# FPGA_-_PERIPHERALS.net
KiCad netlist of a schematic drawn in Altium Designer
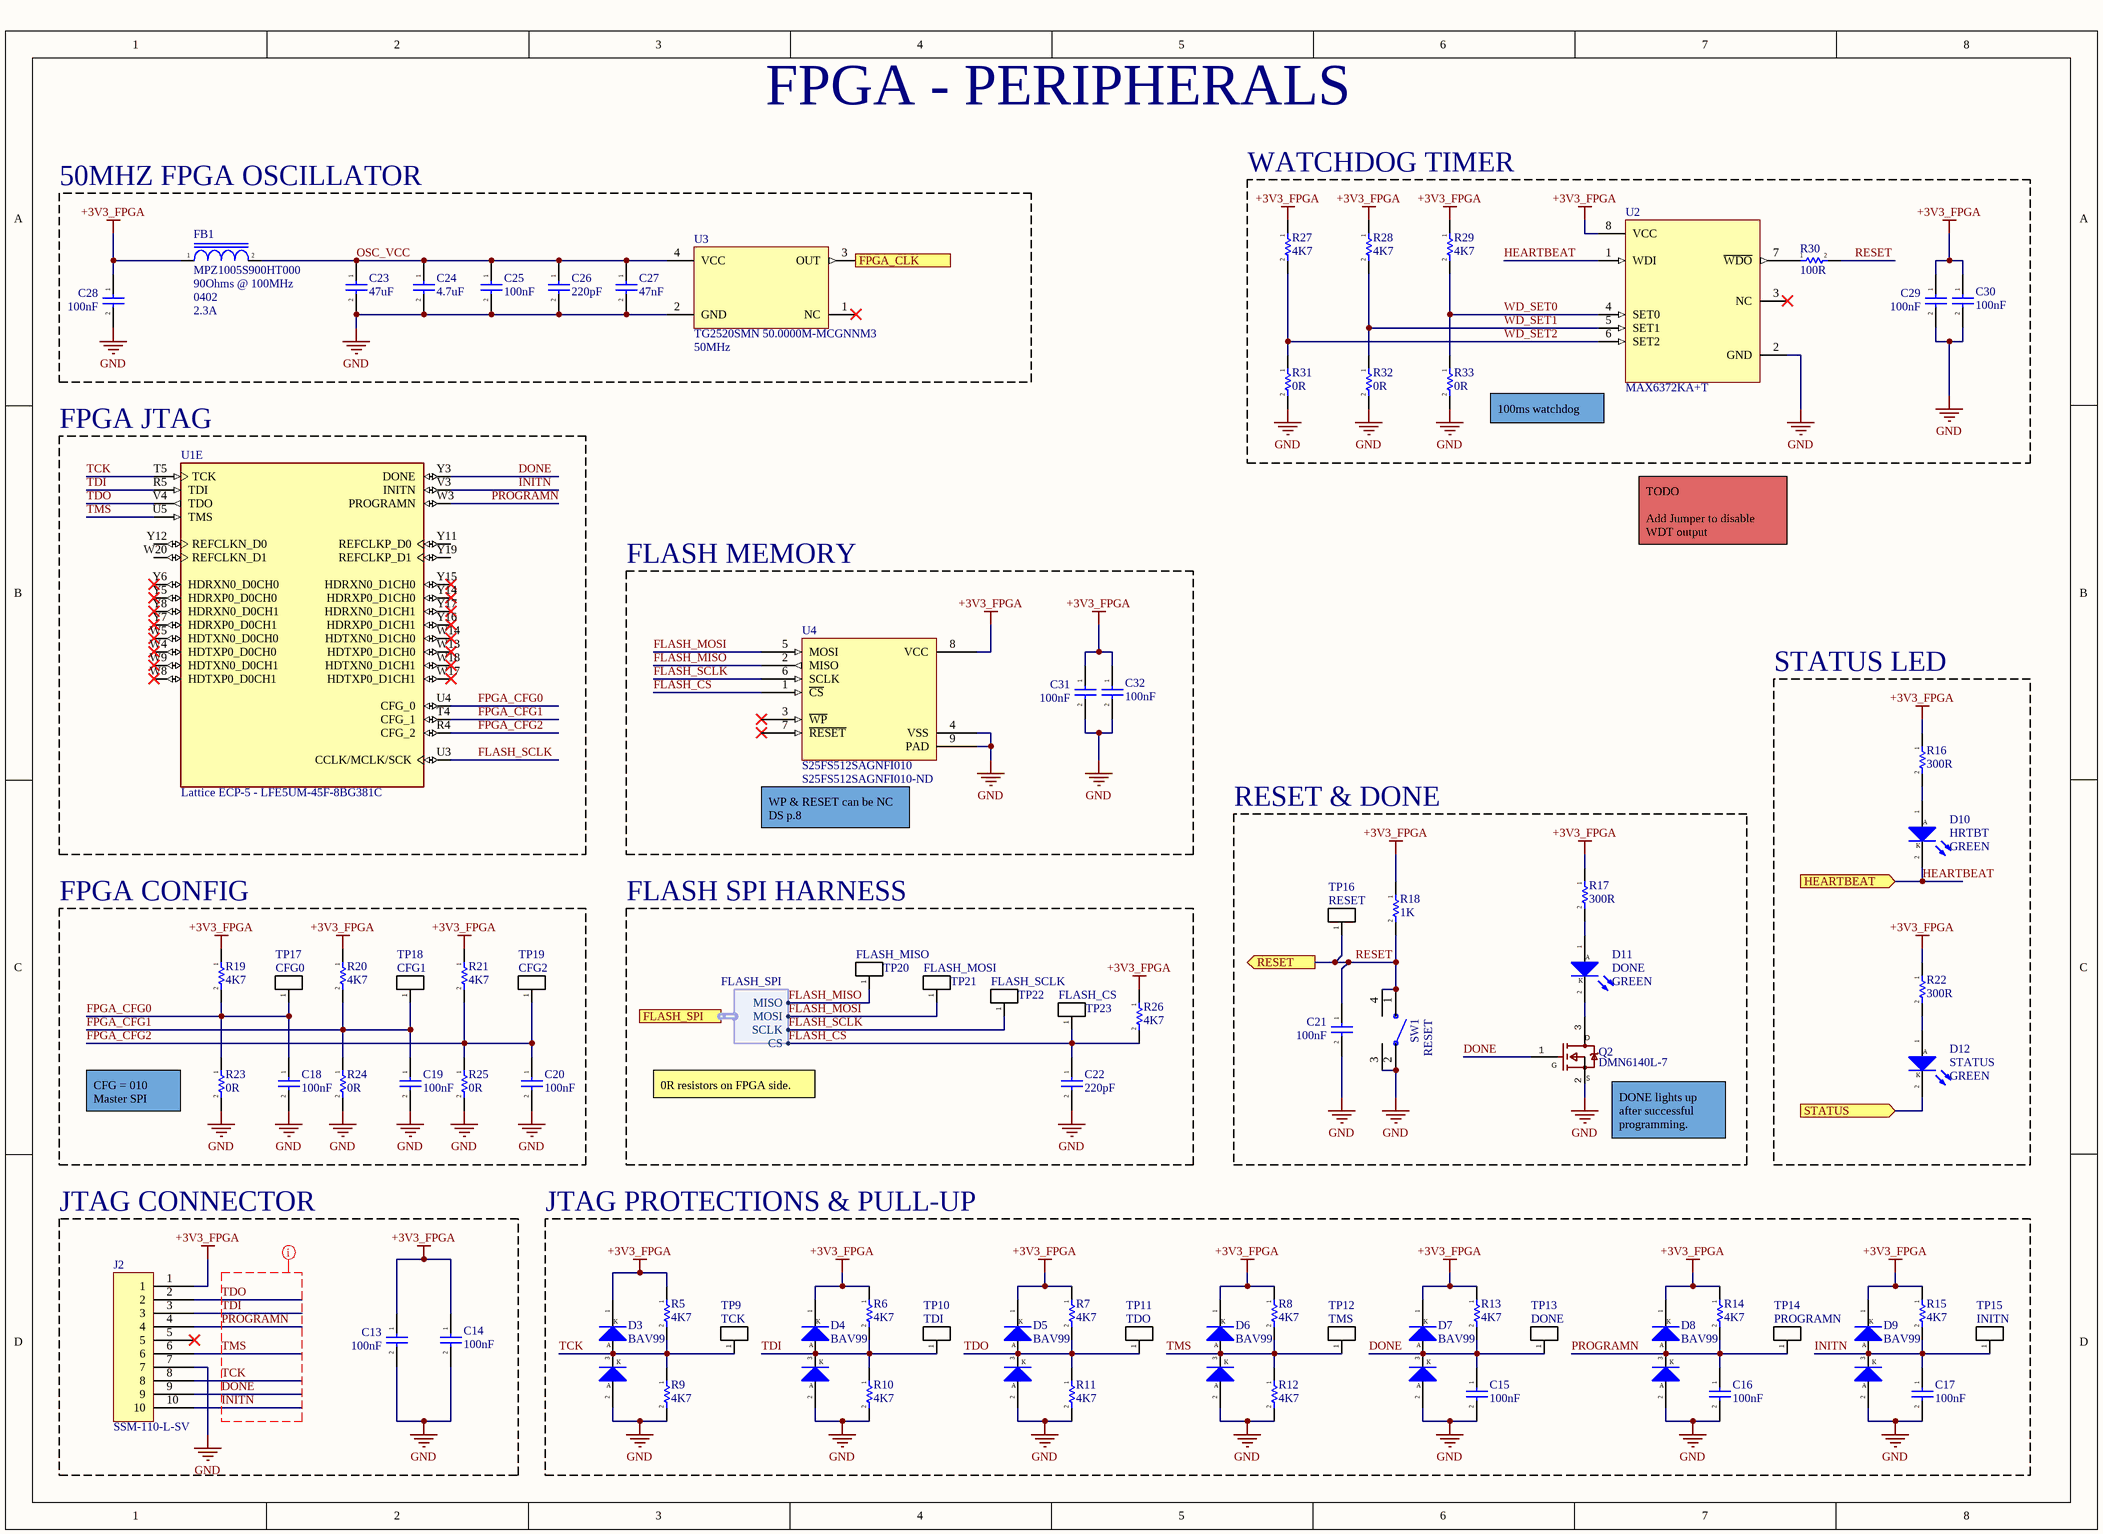
[diagram p0: FPGA - PERIPHERALS.SchDoc]

(export (version "E")
  (design (tool "Eeschema 10.0.6"))
  (components
    (comp (ref "C13")
      (value "100nF")
      (footprint "CAP_0402")
      (description "Generic SMT Ceramic Capacitor")
      (libsource (lib "Symbols") (part "CAP_CER"))
    )
    (comp (ref "C14")
      (value "100nF")
      (footprint "CAP_0402")
      (description "Generic SMT Ceramic Capacitor")
      (libsource (lib "Symbols") (part "CAP_CER"))
    )
    (comp (ref "C15")
      (value "100nF")
      (footprint "CAP_0402")
      (description "Generic SMT Ceramic Capacitor")
      (libsource (lib "Symbols") (part "CAP_CER"))
    )
    (comp (ref "C16")
      (value "100nF")
      (footprint "CAP_0402")
      (description "Generic SMT Ceramic Capacitor")
      (libsource (lib "Symbols") (part "CAP_CER"))
    )
    (comp (ref "C17")
      (value "100nF")
      (footprint "CAP_0402")
      (description "Generic SMT Ceramic Capacitor")
      (libsource (lib "Symbols") (part "CAP_CER"))
    )
    (comp (ref "C18")
      (value "100nF")
      (footprint "CAP_0402")
      (description "Generic SMT Ceramic Capacitor")
      (libsource (lib "Symbols") (part "CAP_CER"))
    )
    (comp (ref "C19")
      (value "100nF")
      (footprint "CAP_0402")
      (description "Generic SMT Ceramic Capacitor")
      (libsource (lib "Symbols") (part "CAP_CER"))
    )
    (comp (ref "C20")
      (value "100nF")
      (footprint "CAP_0402")
      (description "Generic SMT Ceramic Capacitor")
      (libsource (lib "Symbols") (part "CAP_CER"))
    )
    (comp (ref "C21")
      (value "100nF")
      (footprint "CAP_0402")
      (description "Generic SMT Ceramic Capacitor")
      (libsource (lib "Symbols") (part "CAP_CER"))
    )
    (comp (ref "C22")
      (value "220pF")
      (footprint "CAP_0402")
      (description "Generic SMT Ceramic Capacitor")
      (libsource (lib "Symbols") (part "CAP_CER"))
    )
    (comp (ref "C23")
      (value "47uF")
      (footprint "CAP_1206")
      (description "Generic SMT Ceramic Capacitor")
      (libsource (lib "Symbols") (part "CAP_CER"))
    )
    (comp (ref "C24")
      (value "4.7uF")
      (footprint "CAP_0805")
      (description "Generic SMT Ceramic Capacitor")
      (libsource (lib "Symbols") (part "CAP_CER"))
    )
    (comp (ref "C25")
      (value "100nF")
      (footprint "CAP_0402")
      (description "Generic SMT Ceramic Capacitor")
      (libsource (lib "Symbols") (part "CAP_CER"))
    )
    (comp (ref "C26")
      (value "220pF")
      (footprint "CAP_0402")
      (description "Generic SMT Ceramic Capacitor")
      (libsource (lib "Symbols") (part "CAP_CER"))
    )
    (comp (ref "C27")
      (value "47nF")
      (footprint "CAP_0201")
      (description "Generic SMT Ceramic Capacitor")
      (libsource (lib "Symbols") (part "CAP_CER"))
    )
    (comp (ref "C28")
      (value "100nF")
      (footprint "CAP_0402")
      (description "Generic SMT Ceramic Capacitor")
      (libsource (lib "Symbols") (part "CAP_CER"))
    )
    (comp (ref "C29")
      (value "100nF")
      (footprint "CAP_0402")
      (description "Generic SMT Ceramic Capacitor")
      (libsource (lib "Symbols") (part "CAP_CER"))
    )
    (comp (ref "C30")
      (value "100nF")
      (footprint "CAP_0402")
      (description "Generic SMT Ceramic Capacitor")
      (libsource (lib "Symbols") (part "CAP_CER"))
    )
    (comp (ref "C31")
      (value "100nF")
      (footprint "CAP_0402")
      (description "Generic SMT Ceramic Capacitor")
      (libsource (lib "Symbols") (part "CAP_CER"))
    )
    (comp (ref "C32")
      (value "100nF")
      (footprint "CAP_0402")
      (description "Generic SMT Ceramic Capacitor")
      (libsource (lib "Symbols") (part "CAP_CER"))
    )
    (comp (ref "D3")
      (value "BAV99")
      (footprint "MMBD7000-7-F")
      (description "DIODE ARRAY GP 75V 300MA SOT23-3")
      (fields (field (name "MFR") "Taiwan Semiconductor Corporation"))
      (libsource (lib "CryptLib") (part "DIODE_BAV99"))
    )
    (comp (ref "D4")
      (value "BAV99")
      (footprint "MMBD7000-7-F")
      (description "DIODE ARRAY GP 75V 300MA SOT23-3")
      (fields (field (name "MFR") "Taiwan Semiconductor Corporation"))
      (libsource (lib "CryptLib") (part "DIODE_BAV99"))
    )
    (comp (ref "D5")
      (value "BAV99")
      (footprint "MMBD7000-7-F")
      (description "DIODE ARRAY GP 75V 300MA SOT23-3")
      (fields (field (name "MFR") "Taiwan Semiconductor Corporation"))
      (libsource (lib "CryptLib") (part "DIODE_BAV99"))
    )
    (comp (ref "D6")
      (value "BAV99")
      (footprint "MMBD7000-7-F")
      (description "DIODE ARRAY GP 75V 300MA SOT23-3")
      (fields (field (name "MFR") "Taiwan Semiconductor Corporation"))
      (libsource (lib "CryptLib") (part "DIODE_BAV99"))
    )
    (comp (ref "D7")
      (value "BAV99")
      (footprint "MMBD7000-7-F")
      (description "DIODE ARRAY GP 75V 300MA SOT23-3")
      (fields (field (name "MFR") "Taiwan Semiconductor Corporation"))
      (libsource (lib "CryptLib") (part "DIODE_BAV99"))
    )
    (comp (ref "D8")
      (value "BAV99")
      (footprint "MMBD7000-7-F")
      (description "DIODE ARRAY GP 75V 300MA SOT23-3")
      (fields (field (name "MFR") "Taiwan Semiconductor Corporation"))
      (libsource (lib "CryptLib") (part "DIODE_BAV99"))
    )
    (comp (ref "D9")
      (value "BAV99")
      (footprint "MMBD7000-7-F")
      (description "DIODE ARRAY GP 75V 300MA SOT23-3")
      (fields (field (name "MFR") "Taiwan Semiconductor Corporation"))
      (libsource (lib "CryptLib") (part "DIODE_BAV99"))
    )
    (comp (ref "D10")
      (value "HRTBT")
      (footprint "LED_0402")
      (description "Generic LED")
      (fields (field (name "COLOR") "GREEN"))
      (libsource (lib "RaesLib") (part "DIODE_LED"))
    )
    (comp (ref "D11")
      (value "DONE")
      (footprint "LED_0402")
      (description "Generic LED")
      (fields (field (name "COLOR") "GREEN"))
      (libsource (lib "RaesLib") (part "DIODE_LED"))
    )
    (comp (ref "D12")
      (value "STATUS")
      (footprint "LED_0402")
      (description "Generic LED")
      (fields (field (name "COLOR") "GREEN"))
      (libsource (lib "RaesLib") (part "DIODE_LED"))
    )
    (comp (ref "FB1")
      (value "MPZ1005S900HT000")
      (footprint "IND_0402")
      (description "90 Ohms @ 100 MHz 1 Power Line Ferrite Bead 0402 (1005 Metric) 2.3A 38mOhm")
      (fields
        (field (name "IMPEDANCE @ FREQ") "90Ohms @ 100MHz")
        (field (name "PACKAGE / CASE") "0402")
        (field (name "CURRENT RATING") "2.3A")
      )
      (libsource (lib "CryptLib") (part "IND_MPZ1005S900HT000"))
    )
    (comp (ref "J2")
      (value "SSM-110-L-SV")
      (footprint "SSM-110-L-SV")
      (description "CONN RCPT 10POS 0.1 GOLD SMD")
      (fields (field (name "MFR") "Samtec Inc."))
      (libsource (lib "CryptLib") (part "CONN_SSM-110-L-SV"))
    )
    (comp (ref "Q2")
      (value "DMN6140L-7")
      (footprint "SOT23-3")
      (description "N-Channel 60 V 1.6A (Ta) 700mW (Ta) Surface Mount SOT-23")
      (fields (field (name "MFR") "Diodes Incorporated"))
      (libsource (lib "CryptLib") (part "TRANS_DMN6140L-7"))
    )
    (comp (ref "R5")
      (value "4K7")
      (footprint "RES_0603")
      (description "Resistor")
      (fields (field (name "POWER") "1/16W") (field (name "TOLERANCE") "10%"))
      (libsource (lib "Symbols") (part "RESISTOR"))
    )
    (comp (ref "R6")
      (value "4K7")
      (footprint "RES_0603")
      (description "Resistor")
      (fields (field (name "POWER") "1/16W") (field (name "TOLERANCE") "10%"))
      (libsource (lib "Symbols") (part "RESISTOR"))
    )
    (comp (ref "R7")
      (value "4K7")
      (footprint "RES_0603")
      (description "Resistor")
      (fields (field (name "POWER") "1/16W") (field (name "TOLERANCE") "10%"))
      (libsource (lib "Symbols") (part "RESISTOR"))
    )
    (comp (ref "R8")
      (value "4K7")
      (footprint "RES_0603")
      (description "Resistor")
      (fields (field (name "POWER") "1/16W") (field (name "TOLERANCE") "10%"))
      (libsource (lib "Symbols") (part "RESISTOR"))
    )
    (comp (ref "R9")
      (value "4K7")
      (footprint "RES_0603")
      (description "Resistor")
      (fields (field (name "POWER") "1/16W") (field (name "TOLERANCE") "10%"))
      (libsource (lib "Symbols") (part "RESISTOR"))
    )
    (comp (ref "R10")
      (value "4K7")
      (footprint "RES_0603")
      (description "Resistor")
      (fields (field (name "POWER") "1/16W") (field (name "TOLERANCE") "10%"))
      (libsource (lib "Symbols") (part "RESISTOR"))
    )
    (comp (ref "R11")
      (value "4K7")
      (footprint "RES_0603")
      (description "Resistor")
      (fields (field (name "POWER") "1/16W") (field (name "TOLERANCE") "10%"))
      (libsource (lib "Symbols") (part "RESISTOR"))
    )
    (comp (ref "R12")
      (value "4K7")
      (footprint "RES_0603")
      (description "Resistor")
      (fields (field (name "POWER") "1/16W") (field (name "TOLERANCE") "10%"))
      (libsource (lib "Symbols") (part "RESISTOR"))
    )
    (comp (ref "R13")
      (value "4K7")
      (footprint "RES_0603")
      (description "Resistor")
      (fields (field (name "POWER") "1/16W") (field (name "TOLERANCE") "10%"))
      (libsource (lib "Symbols") (part "RESISTOR"))
    )
    (comp (ref "R14")
      (value "4K7")
      (footprint "RES_0603")
      (description "Resistor")
      (fields (field (name "POWER") "1/16W") (field (name "TOLERANCE") "10%"))
      (libsource (lib "Symbols") (part "RESISTOR"))
    )
    (comp (ref "R15")
      (value "4K7")
      (footprint "RES_0603")
      (description "Resistor")
      (fields (field (name "POWER") "1/16W") (field (name "TOLERANCE") "10%"))
      (libsource (lib "Symbols") (part "RESISTOR"))
    )
    (comp (ref "R16")
      (value "300R")
      (footprint "RES_0603")
      (description "Resistor")
      (fields (field (name "POWER") "1/8W") (field (name "TOLERANCE") "2%"))
      (libsource (lib "Symbols") (part "RESISTOR"))
    )
    (comp (ref "R17")
      (value "300R")
      (footprint "RES_0603")
      (description "Resistor")
      (fields (field (name "POWER") "1/8W") (field (name "TOLERANCE") "2%"))
      (libsource (lib "Symbols") (part "RESISTOR"))
    )
    (comp (ref "R18")
      (value "1K")
      (footprint "RES_0603")
      (description "Resistor")
      (fields (field (name "POWER") "1/8W") (field (name "TOLERANCE") "5%"))
      (libsource (lib "Symbols") (part "RESISTOR"))
    )
    (comp (ref "R19")
      (value "4K7")
      (footprint "RES_0603")
      (description "Resistor")
      (fields (field (name "POWER") "1/16W") (field (name "TOLERANCE") "10%"))
      (libsource (lib "Symbols") (part "RESISTOR"))
    )
    (comp (ref "R20")
      (value "4K7")
      (footprint "RES_0603")
      (description "Resistor")
      (fields (field (name "POWER") "1/16W") (field (name "TOLERANCE") "10%"))
      (libsource (lib "Symbols") (part "RESISTOR"))
    )
    (comp (ref "R21")
      (value "4K7")
      (footprint "RES_0603")
      (description "Resistor")
      (fields (field (name "POWER") "1/16W") (field (name "TOLERANCE") "10%"))
      (libsource (lib "Symbols") (part "RESISTOR"))
    )
    (comp (ref "R22")
      (value "300R")
      (footprint "RES_0603")
      (description "Resistor")
      (fields (field (name "POWER") "1/8W") (field (name "TOLERANCE") "2%"))
      (libsource (lib "Symbols") (part "RESISTOR"))
    )
    (comp (ref "R23")
      (value "0R")
      (footprint "RES_0603")
      (description "Resistor")
      (fields (field (name "POWER") "1/8W") (field (name "TOLERANCE") "10%"))
      (libsource (lib "Symbols") (part "RESISTOR"))
    )
    (comp (ref "R24")
      (value "0R")
      (footprint "RES_0603")
      (description "Resistor")
      (fields (field (name "POWER") "1/8W") (field (name "TOLERANCE") "10%"))
      (libsource (lib "Symbols") (part "RESISTOR"))
    )
    (comp (ref "R25")
      (value "0R")
      (footprint "RES_0603")
      (description "Resistor")
      (fields (field (name "POWER") "1/8W") (field (name "TOLERANCE") "10%"))
      (libsource (lib "Symbols") (part "RESISTOR"))
    )
    (comp (ref "R26")
      (value "4K7")
      (footprint "RES_0603")
      (description "Resistor")
      (fields (field (name "POWER") "1/16W") (field (name "TOLERANCE") "10%"))
      (libsource (lib "Symbols") (part "RESISTOR"))
    )
    (comp (ref "R27")
      (value "4K7")
      (footprint "RES_0603")
      (description "Resistor")
      (fields (field (name "POWER") "1/16W") (field (name "TOLERANCE") "10%"))
      (libsource (lib "Symbols") (part "RESISTOR"))
    )
    (comp (ref "R28")
      (value "4K7")
      (footprint "RES_0603")
      (description "Resistor")
      (fields (field (name "POWER") "1/16W") (field (name "TOLERANCE") "10%"))
      (libsource (lib "Symbols") (part "RESISTOR"))
    )
    (comp (ref "R29")
      (value "4K7")
      (footprint "RES_0603")
      (description "Resistor")
      (fields (field (name "POWER") "1/16W") (field (name "TOLERANCE") "10%"))
      (libsource (lib "Symbols") (part "RESISTOR"))
    )
    (comp (ref "R30")
      (value "100R")
      (footprint "RES_0402")
      (description "Resistor")
      (fields (field (name "POWER") "1/8W") (field (name "TOLERANCE") "10%"))
      (libsource (lib "Symbols") (part "RESISTOR"))
    )
    (comp (ref "R31")
      (value "0R")
      (footprint "RES_0603")
      (description "Resistor")
      (fields (field (name "POWER") "1/8W") (field (name "TOLERANCE") "10%"))
      (libsource (lib "Symbols") (part "RESISTOR"))
    )
    (comp (ref "R32")
      (value "0R")
      (footprint "RES_0603")
      (description "Resistor")
      (fields (field (name "POWER") "1/8W") (field (name "TOLERANCE") "10%"))
      (libsource (lib "Symbols") (part "RESISTOR"))
    )
    (comp (ref "R33")
      (value "0R")
      (footprint "RES_0603")
      (description "Resistor")
      (fields (field (name "POWER") "1/8W") (field (name "TOLERANCE") "10%"))
      (libsource (lib "Symbols") (part "RESISTOR"))
    )
    (comp (ref "SW1")
      (value "RESET")
      (footprint "KMR621NGLFS")
      (description "Tactile Switch SPST-NO Top Actuated Surface Mount")
      (fields (field (name "MFR") "C&K") (field (name "ALTERNATIVE PART") "KMR641NG ULC LFS"))
      (libsource (lib "CryptLib") (part "SW_KMR621NG_LFS"))
    )
    (comp (ref "TP9")
      (value "TCK")
      (footprint "TP_PAD_SMALL")
      (description "Test Point")
      (libsource (lib "Symbols") (part "TESTPOINT"))
    )
    (comp (ref "TP10")
      (value "TDI")
      (footprint "TP_PAD_SMALL")
      (description "Test Point")
      (libsource (lib "Symbols") (part "TESTPOINT"))
    )
    (comp (ref "TP11")
      (value "TDO")
      (footprint "TP_PAD_SMALL")
      (description "Test Point")
      (libsource (lib "Symbols") (part "TESTPOINT"))
    )
    (comp (ref "TP12")
      (value "TMS")
      (footprint "TP_PAD_SMALL")
      (description "Test Point")
      (libsource (lib "Symbols") (part "TESTPOINT"))
    )
    (comp (ref "TP13")
      (value "DONE")
      (footprint "TP_PAD_TINY")
      (description "Test Point")
      (libsource (lib "Symbols") (part "TESTPOINT"))
    )
    (comp (ref "TP14")
      (value "PROGRAMN")
      (footprint "TP_PAD_TINY")
      (description "Test Point")
      (libsource (lib "Symbols") (part "TESTPOINT"))
    )
    (comp (ref "TP15")
      (value "INITN")
      (footprint "TP_PAD_TINY")
      (description "Test Point")
      (libsource (lib "Symbols") (part "TESTPOINT"))
    )
    (comp (ref "TP16")
      (value "RESET")
      (footprint "TP_PAD_SMALL")
      (description "Test Point")
      (libsource (lib "Symbols") (part "TESTPOINT"))
    )
    (comp (ref "TP17")
      (value "CFG0")
      (footprint "TP_PAD_TINY")
      (description "Test Point")
      (libsource (lib "Symbols") (part "TESTPOINT"))
    )
    (comp (ref "TP18")
      (value "CFG1")
      (footprint "TP_PAD_TINY")
      (description "Test Point")
      (libsource (lib "Symbols") (part "TESTPOINT"))
    )
    (comp (ref "TP19")
      (value "CFG2")
      (footprint "TP_PAD_TINY")
      (description "Test Point")
      (libsource (lib "Symbols") (part "TESTPOINT"))
    )
    (comp (ref "TP20")
      (value "FLASH_MISO")
      (footprint "TP_PAD_SMALL")
      (description "Test Point")
      (libsource (lib "Symbols") (part "TESTPOINT"))
    )
    (comp (ref "TP21")
      (value "FLASH_MOSI")
      (footprint "TP_PAD_SMALL")
      (description "Test Point")
      (libsource (lib "Symbols") (part "TESTPOINT"))
    )
    (comp (ref "TP22")
      (value "FLASH_SCLK")
      (footprint "TP_PAD_SMALL")
      (description "Test Point")
      (libsource (lib "Symbols") (part "TESTPOINT"))
    )
    (comp (ref "TP23")
      (value "FLASH_CS")
      (footprint "TP_PAD_SMALL")
      (description "Test Point")
      (libsource (lib "Symbols") (part "TESTPOINT"))
    )
    (comp (ref "U1")
      (value "Lattice ECP-5 - LFE5UM-45F-8BG381C")
      (footprint "CABGA-381")
      (description "IC FPGA 203 I/O 381CABGA")
      (fields (field (name "MFR") "Lattice Semiconductors"))
      (libsource (lib "CryptLib") (part "IC_LFE5UM-45F-8BG381C"))
    )
    (comp (ref "U2")
      (value "MAX6372KA+T")
      (footprint "SOT23-8")
      (description "Watchdog Push-Pull, Totem Pole 1 Channel SOT-23-8")
      (fields (field (name "MFR") "Maxim Integrated"))
      (libsource (lib "CryptLib") (part "IC_MAX6372KA-T"))
    )
    (comp (ref "U3")
      (value "TG2520SMN 50.0000M-MCGNNM3")
      (footprint "TG2520SMN")
      (description "50 MHz TCXO Clipped Sine Wave Oscillator 2.8V ~ 3.3V - 4-SMD, No Lead")
      (fields (field (name "MFR") "EPSON") (field (name "FREQUENCY") "50MHz"))
      (libsource (lib "CryptLib") (part "IC_TG2520SMN_50.0000M-MCGNNM3"))
    )
    (comp (ref "U4")
      (value "S25FS512SAGNFI010")
      (footprint "s25FL256LAGNFV010")
      (description "FLASH - NOR Memory IC 512Mb (64M x 8) SPI - Quad I/O, QPI 133 MHz 8-WSON (6x8)")
      (fields (field (name "MFR") "Cypress") (field (name "SUPPLIER PART NUMBER 1") "S25FS512SAGNFI010-ND"))
      (libsource (lib "CryptLib") (part "IC_S25FS512SAGNFI010"))
    )
  )
  (nets
    (net (code "2") (name "+3V3_FPGA") (class "Default")
      (node (ref "C13") (pin "1") (pinfunction "1_1") (pintype "passive"))
      (node (ref "C14") (pin "1") (pinfunction "1_1") (pintype "passive"))
      (node (ref "C28") (pin "1") (pinfunction "1_1") (pintype "passive"))
      (node (ref "C29") (pin "1") (pinfunction "1_1") (pintype "passive"))
      (node (ref "C30") (pin "1") (pinfunction "1_1") (pintype "passive"))
      (node (ref "C31") (pin "1") (pinfunction "1_1") (pintype "passive"))
      (node (ref "C32") (pin "1") (pinfunction "1_1") (pintype "passive"))
      (node (ref "D3") (pin "1") (pinfunction "K_1") (pintype "passive"))
      (node (ref "D4") (pin "1") (pinfunction "K_1") (pintype "passive"))
      (node (ref "D5") (pin "1") (pinfunction "K_1") (pintype "passive"))
      (node (ref "D6") (pin "1") (pinfunction "K_1") (pintype "passive"))
      (node (ref "D7") (pin "1") (pinfunction "K_1") (pintype "passive"))
      (node (ref "D8") (pin "1") (pinfunction "K_1") (pintype "passive"))
      (node (ref "D9") (pin "1") (pinfunction "K_1") (pintype "passive"))
      (node (ref "FB1") (pin "1") (pinfunction "1_1") (pintype "passive"))
      (node (ref "J2") (pin "1") (pinfunction "1_1") (pintype "passive"))
      (node (ref "R13") (pin "1") (pinfunction "1_1") (pintype "passive"))
      (node (ref "R14") (pin "1") (pinfunction "1_1") (pintype "passive"))
      (node (ref "R15") (pin "1") (pinfunction "1_1") (pintype "passive"))
      (node (ref "R16") (pin "1") (pinfunction "1_1") (pintype "passive"))
      (node (ref "R17") (pin "1") (pinfunction "1_1") (pintype "passive"))
      (node (ref "R18") (pin "1") (pinfunction "1_1") (pintype "passive"))
      (node (ref "R19") (pin "1") (pinfunction "1_1") (pintype "passive"))
      (node (ref "R20") (pin "1") (pinfunction "1_1") (pintype "passive"))
      (node (ref "R21") (pin "1") (pinfunction "1_1") (pintype "passive"))
      (node (ref "R22") (pin "1") (pinfunction "1_1") (pintype "passive"))
      (node (ref "R26") (pin "1") (pinfunction "1_1") (pintype "passive"))
      (node (ref "R27") (pin "1") (pinfunction "1_1") (pintype "passive"))
      (node (ref "R28") (pin "1") (pinfunction "1_1") (pintype "passive"))
      (node (ref "R29") (pin "1") (pinfunction "1_1") (pintype "passive"))
      (node (ref "R5") (pin "1") (pinfunction "1_1") (pintype "passive"))
      (node (ref "R6") (pin "1") (pinfunction "1_1") (pintype "passive"))
      (node (ref "R7") (pin "1") (pinfunction "1_1") (pintype "passive"))
      (node (ref "R8") (pin "1") (pinfunction "1_1") (pintype "passive"))
      (node (ref "U2") (pin "8") (pinfunction "VCC_8") (pintype "power_in"))
      (node (ref "U4") (pin "8") (pinfunction "VCC_8") (pintype "power_in"))
    )
    (net (code "3") (name "/DONE") (class "Default")
      (node (ref "C15") (pin "1") (pinfunction "1_1") (pintype "passive"))
      (node (ref "D7") (pin "3") (pinfunction "A_3") (pintype "passive"))
      (node (ref "J2") (pin "9") (pinfunction "9_9") (pintype "passive"))
      (node (ref "Q2") (pin "1") (pintype "passive"))
      (node (ref "R13") (pin "2") (pinfunction "2_2") (pintype "passive"))
      (node (ref "TP13") (pin "1") (pinfunction "A_1") (pintype "passive"))
      (node (ref "U1") (pin "Y3") (pinfunction "DONE_Y3") (pintype "bidirectional"))
    )
    (net (code "4") (name "/FLASH_CS") (class "Default")
      (node (ref "C22") (pin "1") (pinfunction "1_1") (pintype "passive"))
      (node (ref "R26") (pin "2") (pinfunction "2_2") (pintype "passive"))
      (node (ref "TP23") (pin "1") (pinfunction "A_1") (pintype "passive"))
      (node (ref "U4") (pin "1") (pinfunction "~{CS}_1") (pintype "input"))
    )
    (net (code "5") (name "/FLASH_MISO") (class "Default")
      (node (ref "TP20") (pin "1") (pinfunction "A_1") (pintype "passive"))
      (node (ref "U4") (pin "2") (pinfunction "MISO_2") (pintype "output"))
    )
    (net (code "6") (name "/FLASH_MOSI") (class "Default")
      (node (ref "TP21") (pin "1") (pinfunction "A_1") (pintype "passive"))
      (node (ref "U4") (pin "5") (pinfunction "MOSI_5") (pintype "input"))
    )
    (net (code "7") (name "/FLASH_SCLK") (class "Default")
      (node (ref "TP22") (pin "1") (pinfunction "A_1") (pintype "passive"))
      (node (ref "U1") (pin "U3") (pinfunction "CCLK/MCLK/SCK_U3") (pintype "bidirectional"))
      (node (ref "U4") (pin "6") (pinfunction "SCLK_6") (pintype "input"))
    )
    (net (code "8") (name "/FPGA_CFG0") (class "Default")
      (node (ref "C18") (pin "1") (pinfunction "1_1") (pintype "passive"))
      (node (ref "R19") (pin "2") (pinfunction "2_2") (pintype "passive"))
      (node (ref "R23") (pin "1") (pinfunction "1_1") (pintype "passive"))
      (node (ref "TP17") (pin "1") (pinfunction "A_1") (pintype "passive"))
      (node (ref "U1") (pin "U4") (pinfunction "CFG_0_U4") (pintype "bidirectional"))
    )
    (net (code "9") (name "/FPGA_CFG1") (class "Default")
      (node (ref "C19") (pin "1") (pinfunction "1_1") (pintype "passive"))
      (node (ref "R20") (pin "2") (pinfunction "2_2") (pintype "passive"))
      (node (ref "R24") (pin "1") (pinfunction "1_1") (pintype "passive"))
      (node (ref "TP18") (pin "1") (pinfunction "A_1") (pintype "passive"))
      (node (ref "U1") (pin "T4") (pinfunction "CFG_1_T4") (pintype "bidirectional"))
    )
    (net (code "10") (name "/FPGA_CFG2") (class "Default")
      (node (ref "C20") (pin "1") (pinfunction "1_1") (pintype "passive"))
      (node (ref "R21") (pin "2") (pinfunction "2_2") (pintype "passive"))
      (node (ref "R25") (pin "1") (pinfunction "1_1") (pintype "passive"))
      (node (ref "TP19") (pin "1") (pinfunction "A_1") (pintype "passive"))
      (node (ref "U1") (pin "R4") (pinfunction "CFG_2_R4") (pintype "bidirectional"))
    )
    (net (code "11") (name "/FPGA_CLK") (class "Default")
      (node (ref "U3") (pin "3") (pinfunction "OUT_3") (pintype "output"))
    )
    (net (code "12") (name "/HEARTBEAT") (class "Default")
      (node (ref "D10") (pin "2") (pinfunction "K_2") (pintype "passive"))
      (node (ref "U2") (pin "1") (pinfunction "WDI_1") (pintype "input"))
    )
    (net (code "13") (name "/INITN") (class "Default")
      (node (ref "C17") (pin "1") (pinfunction "1_1") (pintype "passive"))
      (node (ref "D9") (pin "3") (pinfunction "A_3") (pintype "passive"))
      (node (ref "J2") (pin "10") (pinfunction "10_10") (pintype "passive"))
      (node (ref "R15") (pin "2") (pinfunction "2_2") (pintype "passive"))
      (node (ref "TP15") (pin "1") (pinfunction "A_1") (pintype "passive"))
      (node (ref "U1") (pin "V3") (pinfunction "INITN_V3") (pintype "bidirectional"))
    )
    (net (code "14") (name "/OSC_VCC") (class "Default")
      (node (ref "C23") (pin "1") (pinfunction "1_1") (pintype "passive"))
      (node (ref "C24") (pin "1") (pinfunction "1_1") (pintype "passive"))
      (node (ref "C25") (pin "1") (pinfunction "1_1") (pintype "passive"))
      (node (ref "C26") (pin "1") (pinfunction "1_1") (pintype "passive"))
      (node (ref "C27") (pin "1") (pinfunction "1_1") (pintype "passive"))
      (node (ref "FB1") (pin "2") (pinfunction "2_2") (pintype "passive"))
      (node (ref "U3") (pin "4") (pinfunction "VCC_4") (pintype "power_in"))
    )
    (net (code "15") (name "/PROGRAMN") (class "Default")
      (node (ref "C16") (pin "1") (pinfunction "1_1") (pintype "passive"))
      (node (ref "D8") (pin "3") (pinfunction "A_3") (pintype "passive"))
      (node (ref "J2") (pin "4") (pinfunction "4_4") (pintype "passive"))
      (node (ref "R14") (pin "2") (pinfunction "2_2") (pintype "passive"))
      (node (ref "TP14") (pin "1") (pinfunction "A_1") (pintype "passive"))
      (node (ref "U1") (pin "W3") (pinfunction "PROGRAMN_W3") (pintype "bidirectional"))
    )
    (net (code "16") (name "/RESET") (class "Default")
      (node (ref "C21") (pin "1") (pinfunction "1_1") (pintype "passive"))
      (node (ref "R18") (pin "2") (pinfunction "2_2") (pintype "passive"))
      (node (ref "R30") (pin "2") (pinfunction "2_2") (pintype "passive"))
      (node (ref "SW1") (pin "1") (pinfunction "1_1") (pintype "passive"))
      (node (ref "SW1") (pin "4") (pinfunction "1_4") (pintype "passive"))
      (node (ref "TP16") (pin "1") (pinfunction "A_1") (pintype "passive"))
    )
    (net (code "17") (name "/STATUS") (class "Default")
      (node (ref "D12") (pin "2") (pinfunction "K_2") (pintype "passive"))
    )
    (net (code "18") (name "/TCK") (class "Default")
      (node (ref "D3") (pin "3") (pinfunction "A_3") (pintype "passive"))
      (node (ref "J2") (pin "8") (pinfunction "8_8") (pintype "passive"))
      (node (ref "R5") (pin "2") (pinfunction "2_2") (pintype "passive"))
      (node (ref "R9") (pin "1") (pinfunction "1_1") (pintype "passive"))
      (node (ref "TP9") (pin "1") (pinfunction "A_1") (pintype "passive"))
      (node (ref "U1") (pin "T5") (pinfunction "TCK_T5") (pintype "input"))
    )
    (net (code "19") (name "/TDI") (class "Default")
      (node (ref "D4") (pin "3") (pinfunction "A_3") (pintype "passive"))
      (node (ref "J2") (pin "3") (pinfunction "3_3") (pintype "passive"))
      (node (ref "R10") (pin "1") (pinfunction "1_1") (pintype "passive"))
      (node (ref "R6") (pin "2") (pinfunction "2_2") (pintype "passive"))
      (node (ref "TP10") (pin "1") (pinfunction "A_1") (pintype "passive"))
      (node (ref "U1") (pin "R5") (pinfunction "TDI_R5") (pintype "input"))
    )
    (net (code "20") (name "/TDO") (class "Default")
      (node (ref "D5") (pin "3") (pinfunction "A_3") (pintype "passive"))
      (node (ref "J2") (pin "2") (pinfunction "2_2") (pintype "passive"))
      (node (ref "R11") (pin "1") (pinfunction "1_1") (pintype "passive"))
      (node (ref "R7") (pin "2") (pinfunction "2_2") (pintype "passive"))
      (node (ref "TP11") (pin "1") (pinfunction "A_1") (pintype "passive"))
      (node (ref "U1") (pin "V4") (pinfunction "TDO_V4") (pintype "output"))
    )
    (net (code "21") (name "/TMS") (class "Default")
      (node (ref "D6") (pin "3") (pinfunction "A_3") (pintype "passive"))
      (node (ref "J2") (pin "6") (pinfunction "6_6") (pintype "passive"))
      (node (ref "R12") (pin "1") (pinfunction "1_1") (pintype "passive"))
      (node (ref "R8") (pin "2") (pinfunction "2_2") (pintype "passive"))
      (node (ref "TP12") (pin "1") (pinfunction "A_1") (pintype "passive"))
      (node (ref "U1") (pin "U5") (pinfunction "TMS_U5") (pintype "input"))
    )
    (net (code "22") (name "/WD_SET0") (class "Default")
      (node (ref "R29") (pin "2") (pinfunction "2_2") (pintype "passive"))
      (node (ref "R33") (pin "1") (pinfunction "1_1") (pintype "passive"))
      (node (ref "U2") (pin "4") (pinfunction "SET0_4") (pintype "input"))
    )
    (net (code "23") (name "/WD_SET1") (class "Default")
      (node (ref "R28") (pin "2") (pinfunction "2_2") (pintype "passive"))
      (node (ref "R32") (pin "1") (pinfunction "1_1") (pintype "passive"))
      (node (ref "U2") (pin "5") (pinfunction "SET1_5") (pintype "input"))
    )
    (net (code "24") (name "/WD_SET2") (class "Default")
      (node (ref "R27") (pin "2") (pinfunction "2_2") (pintype "passive"))
      (node (ref "R31") (pin "1") (pinfunction "1_1") (pintype "passive"))
      (node (ref "U2") (pin "6") (pinfunction "SET2_6") (pintype "input"))
    )
    (net (code "26") (name "GND") (class "Default")
      (node (ref "C13") (pin "2") (pinfunction "2_2") (pintype "passive"))
      (node (ref "C14") (pin "2") (pinfunction "2_2") (pintype "passive"))
      (node (ref "C15") (pin "2") (pinfunction "2_2") (pintype "passive"))
      (node (ref "C16") (pin "2") (pinfunction "2_2") (pintype "passive"))
      (node (ref "C17") (pin "2") (pinfunction "2_2") (pintype "passive"))
      (node (ref "C18") (pin "2") (pinfunction "2_2") (pintype "passive"))
      (node (ref "C19") (pin "2") (pinfunction "2_2") (pintype "passive"))
      (node (ref "C20") (pin "2") (pinfunction "2_2") (pintype "passive"))
      (node (ref "C21") (pin "2") (pinfunction "2_2") (pintype "passive"))
      (node (ref "C22") (pin "2") (pinfunction "2_2") (pintype "passive"))
      (node (ref "C23") (pin "2") (pinfunction "2_2") (pintype "passive"))
      (node (ref "C24") (pin "2") (pinfunction "2_2") (pintype "passive"))
      (node (ref "C25") (pin "2") (pinfunction "2_2") (pintype "passive"))
      (node (ref "C26") (pin "2") (pinfunction "2_2") (pintype "passive"))
      (node (ref "C27") (pin "2") (pinfunction "2_2") (pintype "passive"))
      (node (ref "C28") (pin "2") (pinfunction "2_2") (pintype "passive"))
      (node (ref "C29") (pin "2") (pinfunction "2_2") (pintype "passive"))
      (node (ref "C30") (pin "2") (pinfunction "2_2") (pintype "passive"))
      (node (ref "C31") (pin "2") (pinfunction "2_2") (pintype "passive"))
      (node (ref "C32") (pin "2") (pinfunction "2_2") (pintype "passive"))
      (node (ref "D3") (pin "2") (pinfunction "K_2") (pintype "passive"))
      (node (ref "D4") (pin "2") (pinfunction "K_2") (pintype "passive"))
      (node (ref "D5") (pin "2") (pinfunction "K_2") (pintype "passive"))
      (node (ref "D6") (pin "2") (pinfunction "K_2") (pintype "passive"))
      (node (ref "D7") (pin "2") (pinfunction "K_2") (pintype "passive"))
      (node (ref "D8") (pin "2") (pinfunction "K_2") (pintype "passive"))
      (node (ref "D9") (pin "2") (pinfunction "K_2") (pintype "passive"))
      (node (ref "J2") (pin "7") (pinfunction "7_7") (pintype "passive"))
      (node (ref "Q2") (pin "2") (pintype "passive"))
      (node (ref "R10") (pin "2") (pinfunction "2_2") (pintype "passive"))
      (node (ref "R11") (pin "2") (pinfunction "2_2") (pintype "passive"))
      (node (ref "R12") (pin "2") (pinfunction "2_2") (pintype "passive"))
      (node (ref "R23") (pin "2") (pinfunction "2_2") (pintype "passive"))
      (node (ref "R24") (pin "2") (pinfunction "2_2") (pintype "passive"))
      (node (ref "R25") (pin "2") (pinfunction "2_2") (pintype "passive"))
      (node (ref "R31") (pin "2") (pinfunction "2_2") (pintype "passive"))
      (node (ref "R32") (pin "2") (pinfunction "2_2") (pintype "passive"))
      (node (ref "R33") (pin "2") (pinfunction "2_2") (pintype "passive"))
      (node (ref "R9") (pin "2") (pinfunction "2_2") (pintype "passive"))
      (node (ref "SW1") (pin "2") (pinfunction "2_2") (pintype "passive"))
      (node (ref "SW1") (pin "3") (pinfunction "2_3") (pintype "passive"))
      (node (ref "U2") (pin "2") (pinfunction "GND_2") (pintype "power_in"))
      (node (ref "U3") (pin "2") (pinfunction "GND_2") (pintype "power_in"))
      (node (ref "U4") (pin "4") (pinfunction "VSS_4") (pintype "power_in"))
      (node (ref "U4") (pin "9") (pinfunction "PAD_9") (pintype "power_in"))
    )
    (net (code "27") (name "Net-(D10-A)") (class "Default")
      (node (ref "D10") (pin "1") (pinfunction "A_1") (pintype "passive"))
      (node (ref "R16") (pin "2") (pinfunction "2_2") (pintype "passive"))
    )
    (net (code "28") (name "Net-(D11-A)") (class "Default")
      (node (ref "D11") (pin "1") (pinfunction "A_1") (pintype "passive"))
      (node (ref "R17") (pin "2") (pinfunction "2_2") (pintype "passive"))
    )
    (net (code "29") (name "Net-(D11-K)") (class "Default")
      (node (ref "D11") (pin "2") (pinfunction "K_2") (pintype "passive"))
      (node (ref "Q2") (pin "3") (pintype "passive"))
    )
    (net (code "30") (name "Net-(D12-A)") (class "Default")
      (node (ref "D12") (pin "1") (pinfunction "A_1") (pintype "passive"))
      (node (ref "R22") (pin "2") (pinfunction "2_2") (pintype "passive"))
    )
    (net (code "31") (name "Net-(U2-~{WDO})") (class "Default")
      (node (ref "R30") (pin "1") (pinfunction "1_1") (pintype "passive"))
      (node (ref "U2") (pin "7") (pinfunction "~{WDO}_7") (pintype "output"))
    )
    (net (code "32") (name "unconnected-(J2-Pad5)") (class "Default")
      (node (ref "J2") (pin "5") (pinfunction "5_5") (pintype "passive+no_connect"))
    )
    (net (code "33") (name "unconnected-(U1E-HDRXN0_D0CH0-PadY6)") (class "Default")
      (node (ref "U1") (pin "Y6") (pinfunction "HDRXN0_D0CH0_Y6") (pintype "bidirectional+no_connect"))
    )
    (net (code "34") (name "unconnected-(U1E-HDRXN0_D0CH1-PadY8)") (class "Default")
      (node (ref "U1") (pin "Y8") (pinfunction "HDRXN0_D0CH1_Y8") (pintype "bidirectional+no_connect"))
    )
    (net (code "35") (name "unconnected-(U1E-HDRXN0_D1CH0-PadY15)") (class "Default")
      (node (ref "U1") (pin "Y15") (pinfunction "HDRXN0_D1CH0_Y15") (pintype "bidirectional+no_connect"))
    )
    (net (code "36") (name "unconnected-(U1E-HDRXN0_D1CH1-PadY17)") (class "Default")
      (node (ref "U1") (pin "Y17") (pinfunction "HDRXN0_D1CH1_Y17") (pintype "bidirectional+no_connect"))
    )
    (net (code "37") (name "unconnected-(U1E-HDRXP0_D0CH0-PadY5)") (class "Default")
      (node (ref "U1") (pin "Y5") (pinfunction "HDRXP0_D0CH0_Y5") (pintype "bidirectional+no_connect"))
    )
    (net (code "38") (name "unconnected-(U1E-HDRXP0_D0CH1-PadY7)") (class "Default")
      (node (ref "U1") (pin "Y7") (pinfunction "HDRXP0_D0CH1_Y7") (pintype "bidirectional+no_connect"))
    )
    (net (code "39") (name "unconnected-(U1E-HDRXP0_D1CH0-PadY14)") (class "Default")
      (node (ref "U1") (pin "Y14") (pinfunction "HDRXP0_D1CH0_Y14") (pintype "bidirectional+no_connect"))
    )
    (net (code "40") (name "unconnected-(U1E-HDRXP0_D1CH1-PadY16)") (class "Default")
      (node (ref "U1") (pin "Y16") (pinfunction "HDRXP0_D1CH1_Y16") (pintype "bidirectional+no_connect"))
    )
    (net (code "41") (name "unconnected-(U1E-HDTXN0_D0CH0-PadW5)") (class "Default")
      (node (ref "U1") (pin "W5") (pinfunction "HDTXN0_D0CH0_W5") (pintype "bidirectional+no_connect"))
    )
    (net (code "42") (name "unconnected-(U1E-HDTXN0_D0CH1-PadW9)") (class "Default")
      (node (ref "U1") (pin "W9") (pinfunction "HDTXN0_D0CH1_W9") (pintype "bidirectional+no_connect"))
    )
    (net (code "43") (name "unconnected-(U1E-HDTXN0_D1CH0-PadW14)") (class "Default")
      (node (ref "U1") (pin "W14") (pinfunction "HDTXN0_D1CH0_W14") (pintype "bidirectional+no_connect"))
    )
    (net (code "44") (name "unconnected-(U1E-HDTXN0_D1CH1-PadW18)") (class "Default")
      (node (ref "U1") (pin "W18") (pinfunction "HDTXN0_D1CH1_W18") (pintype "bidirectional+no_connect"))
    )
    (net (code "45") (name "unconnected-(U1E-HDTXP0_D0CH0-PadW4)") (class "Default")
      (node (ref "U1") (pin "W4") (pinfunction "HDTXP0_D0CH0_W4") (pintype "bidirectional+no_connect"))
    )
    (net (code "46") (name "unconnected-(U1E-HDTXP0_D0CH1-PadW8)") (class "Default")
      (node (ref "U1") (pin "W8") (pinfunction "HDTXP0_D0CH1_W8") (pintype "bidirectional+no_connect"))
    )
    (net (code "47") (name "unconnected-(U1E-HDTXP0_D1CH0-PadW13)") (class "Default")
      (node (ref "U1") (pin "W13") (pinfunction "HDTXP0_D1CH0_W13") (pintype "bidirectional+no_connect"))
    )
    (net (code "48") (name "unconnected-(U1E-HDTXP0_D1CH1-PadW17)") (class "Default")
      (node (ref "U1") (pin "W17") (pinfunction "HDTXP0_D1CH1_W17") (pintype "bidirectional+no_connect"))
    )
    (net (code "49") (name "unconnected-(U1E-REFCLKN_D0-PadY12)") (class "Default")
      (node (ref "U1") (pin "Y12") (pinfunction "REFCLKN_D0_Y12") (pintype "bidirectional"))
    )
    (net (code "50") (name "unconnected-(U1E-REFCLKN_D1-PadW20)") (class "Default")
      (node (ref "U1") (pin "W20") (pinfunction "REFCLKN_D1_W20") (pintype "bidirectional"))
    )
    (net (code "51") (name "unconnected-(U1E-REFCLKP_D0-PadY11)") (class "Default")
      (node (ref "U1") (pin "Y11") (pinfunction "REFCLKP_D0_Y11") (pintype "bidirectional"))
    )
    (net (code "52") (name "unconnected-(U1E-REFCLKP_D1-PadY19)") (class "Default")
      (node (ref "U1") (pin "Y19") (pinfunction "REFCLKP_D1_Y19") (pintype "bidirectional"))
    )
    (net (code "53") (name "unconnected-(U2-NC-Pad3)") (class "Default")
      (node (ref "U2") (pin "3") (pinfunction "NC_3") (pintype "passive+no_connect"))
    )
    (net (code "54") (name "unconnected-(U3-NC-Pad1)") (class "Default")
      (node (ref "U3") (pin "1") (pinfunction "NC_1") (pintype "passive+no_connect"))
    )
    (net (code "55") (name "unconnected-(U4-~{RESET}-Pad7)") (class "Default")
      (node (ref "U4") (pin "7") (pinfunction "~{RESET}_7") (pintype "input+no_connect"))
    )
    (net (code "56") (name "unconnected-(U4-~{WP}-Pad3)") (class "Default")
      (node (ref "U4") (pin "3") (pinfunction "~{WP}_3") (pintype "input+no_connect"))
    )
  )
)
